# Line_Follower.net
KiCad netlist of a schematic drawn in EAGLE
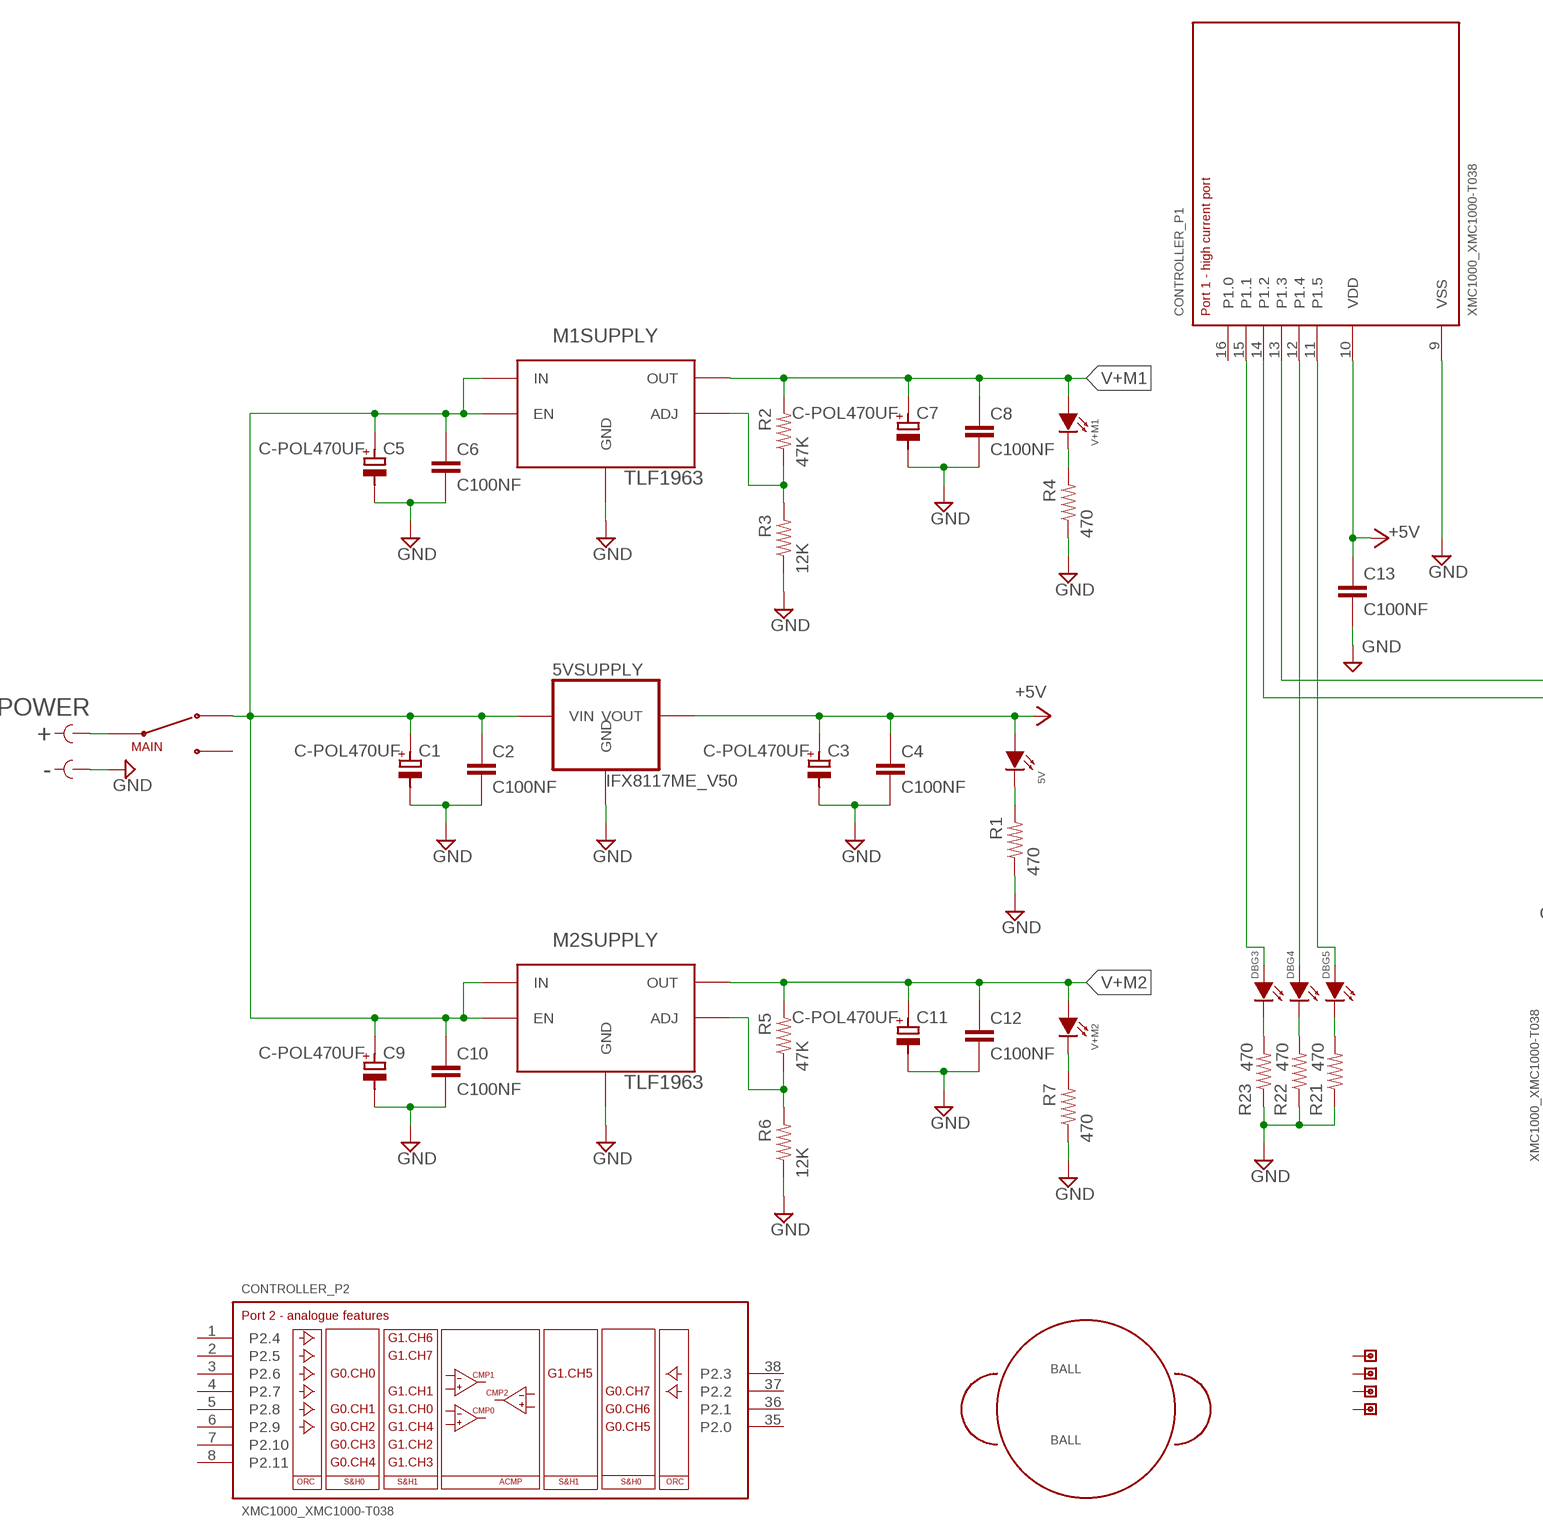
[diagram p0: schematic, sheet 1, part 1 of 2]
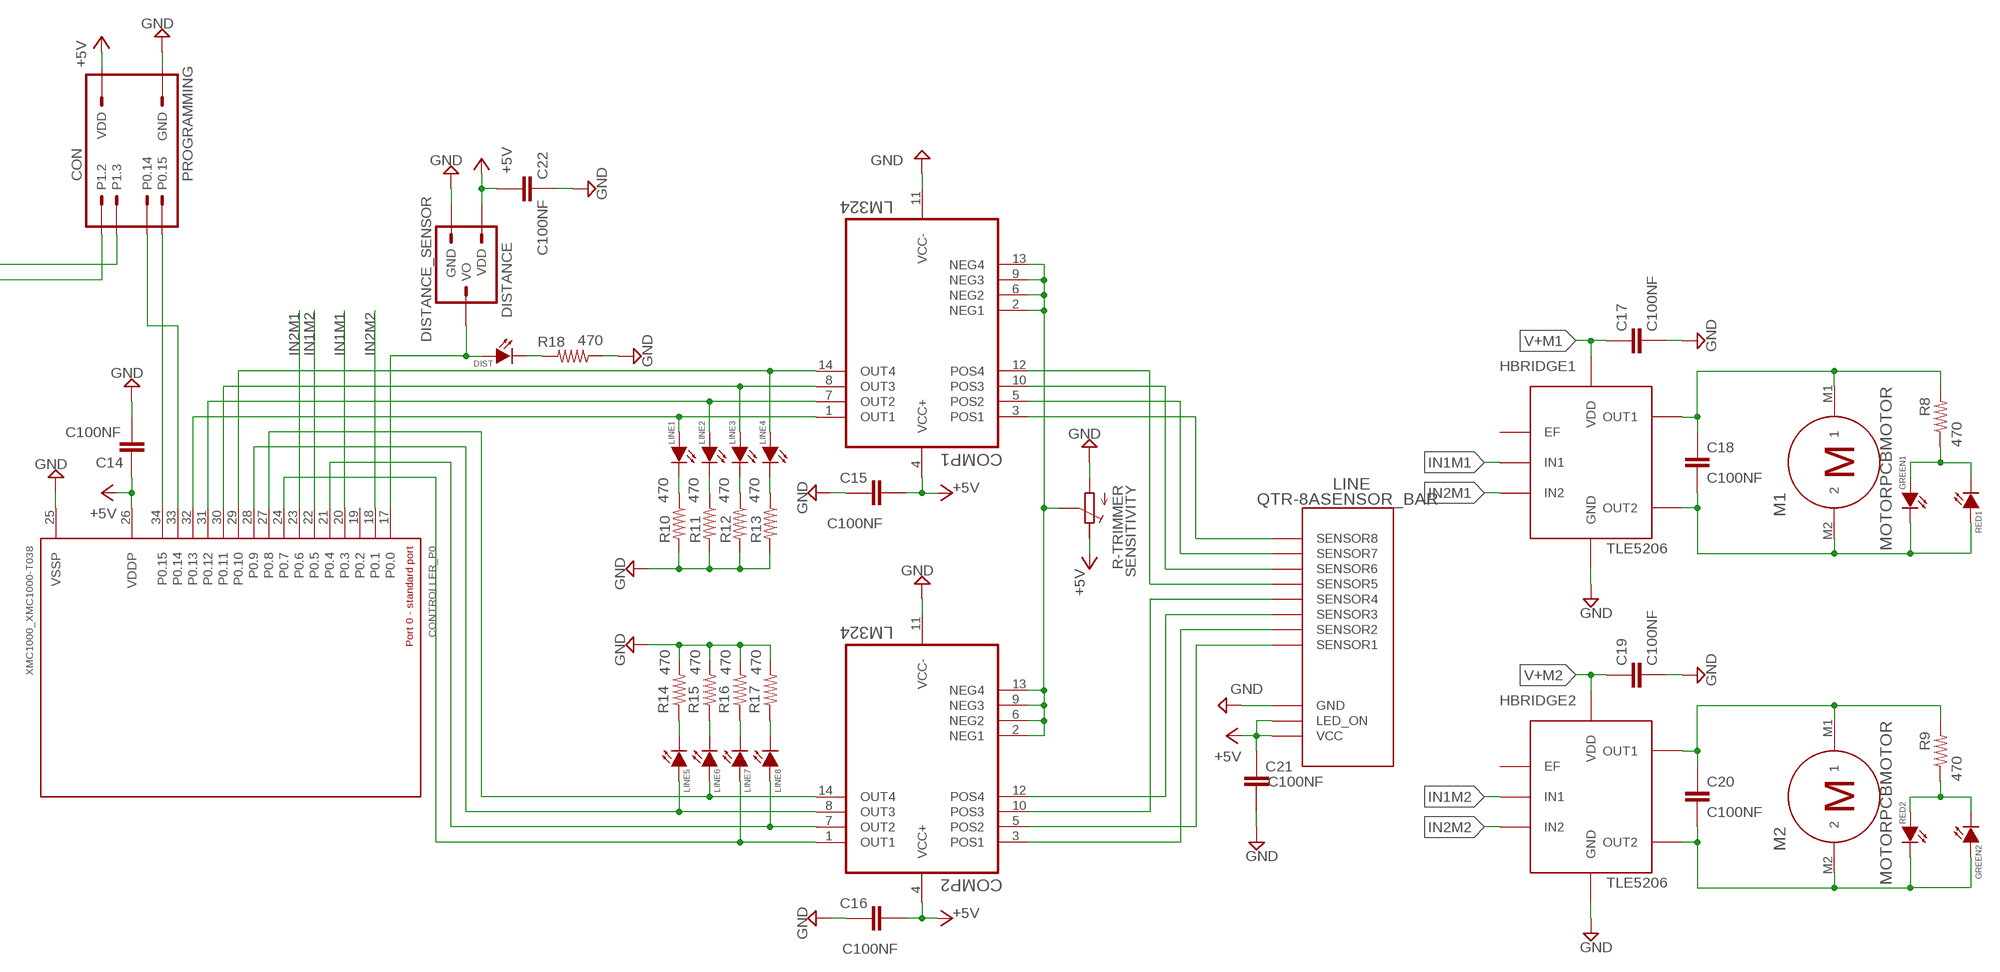
[diagram p1: schematic, sheet 1, part 2 of 2]

(export (version "E")
  (design (tool "Eeschema 10.0.6"))
  (components
    (comp (ref "5V")
      (value "LED")
      (footprint "eagle-import:CHIPLED_1206")
      (libsource (lib "eagle-import") (part "LED"))
    )
    (comp (ref "5VSUPPLY")
      (value "IFX8117ME_V50")
      (footprint "eagle-import:INF-PG-SOT223_SC-73_M_1PRIMARY")
      (libsource (lib "eagle-import") (part "IFX8117ME_V50"))
    )
    (comp (ref "BALL")
      (value "BALL")
      (footprint "eagle-import:BALL")
      (libsource (lib "eagle-import") (part "BALL"))
    )
    (comp (ref "C1")
      (value "C-POL470UF")
      (footprint "eagle-import:E3,5-8")
      (libsource (lib "eagle-import") (part "C-POL470UF"))
    )
    (comp (ref "C2")
      (value "C100NF")
      (footprint "eagle-import:C1206")
      (libsource (lib "eagle-import") (part "C100NF"))
    )
    (comp (ref "C3")
      (value "C-POL470UF")
      (footprint "eagle-import:E3,5-8")
      (libsource (lib "eagle-import") (part "C-POL470UF"))
    )
    (comp (ref "C4")
      (value "C100NF")
      (footprint "eagle-import:C1206")
      (libsource (lib "eagle-import") (part "C100NF"))
    )
    (comp (ref "C5")
      (value "C-POL470UF")
      (footprint "eagle-import:E3,5-8")
      (libsource (lib "eagle-import") (part "C-POL470UF"))
    )
    (comp (ref "C6")
      (value "C100NF")
      (footprint "eagle-import:C1206")
      (libsource (lib "eagle-import") (part "C100NF"))
    )
    (comp (ref "C7")
      (value "C-POL470UF")
      (footprint "eagle-import:E3,5-8")
      (libsource (lib "eagle-import") (part "C-POL470UF"))
    )
    (comp (ref "C8")
      (value "C100NF")
      (footprint "eagle-import:C1206")
      (libsource (lib "eagle-import") (part "C100NF"))
    )
    (comp (ref "C9")
      (value "C-POL470UF")
      (footprint "eagle-import:E3,5-8")
      (libsource (lib "eagle-import") (part "C-POL470UF"))
    )
    (comp (ref "C10")
      (value "C100NF")
      (footprint "eagle-import:C1206")
      (libsource (lib "eagle-import") (part "C100NF"))
    )
    (comp (ref "C11")
      (value "C-POL470UF")
      (footprint "eagle-import:E3,5-8")
      (libsource (lib "eagle-import") (part "C-POL470UF"))
    )
    (comp (ref "C12")
      (value "C100NF")
      (footprint "eagle-import:C1206")
      (libsource (lib "eagle-import") (part "C100NF"))
    )
    (comp (ref "C13")
      (value "C100NF")
      (footprint "eagle-import:C1206")
      (libsource (lib "eagle-import") (part "C100NF"))
    )
    (comp (ref "C14")
      (value "C100NF")
      (footprint "eagle-import:C1206")
      (libsource (lib "eagle-import") (part "C100NF"))
    )
    (comp (ref "C15")
      (value "C100NF")
      (footprint "eagle-import:C1206")
      (libsource (lib "eagle-import") (part "C100NF"))
    )
    (comp (ref "C16")
      (value "C100NF")
      (footprint "eagle-import:C1206")
      (libsource (lib "eagle-import") (part "C100NF"))
    )
    (comp (ref "C17")
      (value "C100NF")
      (footprint "eagle-import:C1206")
      (libsource (lib "eagle-import") (part "C100NF"))
    )
    (comp (ref "C18")
      (value "C100NF")
      (footprint "eagle-import:C1206")
      (libsource (lib "eagle-import") (part "C100NF"))
    )
    (comp (ref "C19")
      (value "C100NF")
      (footprint "eagle-import:C1206")
      (libsource (lib "eagle-import") (part "C100NF"))
    )
    (comp (ref "C20")
      (value "C100NF")
      (footprint "eagle-import:C1206")
      (libsource (lib "eagle-import") (part "C100NF"))
    )
    (comp (ref "C21")
      (value "C100NF")
      (footprint "eagle-import:C1206")
      (libsource (lib "eagle-import") (part "C100NF"))
    )
    (comp (ref "C22")
      (value "C100NF")
      (footprint "eagle-import:C1206")
      (libsource (lib "eagle-import") (part "C100NF"))
    )
    (comp (ref "COMP1")
      (value "LM324")
      (footprint "eagle-import:SO14")
      (libsource (lib "eagle-import") (part "LM324"))
    )
    (comp (ref "COMP2")
      (value "LM324")
      (footprint "eagle-import:SO14")
      (libsource (lib "eagle-import") (part "LM324"))
    )
    (comp (ref "CON")
      (value "PROGRAMMING")
      (footprint "eagle-import:MA05-2")
      (libsource (lib "eagle-import") (part "PROGRAMMING"))
    )
    (comp (ref "CONTROLLER")
      (value "XMC1000_XMC1000-T038")
      (footprint "eagle-import:XMC1000_P-TSSOP38-9")
      (libsource (lib "eagle-import") (part "XMC1000_XMC1000-T038"))
    )
    (comp (ref "DBG3")
      (value "LED")
      (footprint "eagle-import:CHIPLED_1206")
      (libsource (lib "eagle-import") (part "LED"))
    )
    (comp (ref "DBG4")
      (value "LED")
      (footprint "eagle-import:CHIPLED_1206")
      (libsource (lib "eagle-import") (part "LED"))
    )
    (comp (ref "DBG5")
      (value "LED")
      (footprint "eagle-import:CHIPLED_1206")
      (libsource (lib "eagle-import") (part "LED"))
    )
    (comp (ref "DIST")
      (value "LED")
      (footprint "eagle-import:CHIPLED_1206")
      (libsource (lib "eagle-import") (part "LED"))
    )
    (comp (ref "DISTANCE")
      (value "DISTANCE_SENSOR")
      (footprint "eagle-import:MA03-2")
      (libsource (lib "eagle-import") (part "DISTANCE_SENSOR"))
    )
    (comp (ref "GREEN1")
      (value "LED")
      (footprint "eagle-import:CHIPLED_1206")
      (libsource (lib "eagle-import") (part "LED"))
    )
    (comp (ref "GREEN2")
      (value "LED")
      (footprint "eagle-import:CHIPLED_1206")
      (libsource (lib "eagle-import") (part "LED"))
    )
    (comp (ref "HBRIDGE1")
      (value "TLE5206")
      (footprint "eagle-import:INF-PG-TO263-7-1_L_1PRIMARY")
      (libsource (lib "eagle-import") (part "TLE5206"))
    )
    (comp (ref "HBRIDGE2")
      (value "TLE5206")
      (footprint "eagle-import:INF-PG-TO263-7-1_L_1PRIMARY")
      (libsource (lib "eagle-import") (part "TLE5206"))
    )
    (comp (ref "LINE")
      (value "QTR-8ASENSOR_BAR")
      (footprint "eagle-import:QTR-8A")
      (libsource (lib "eagle-import") (part "QTR-8ASENSOR_BAR"))
    )
    (comp (ref "LINE1")
      (value "LED")
      (footprint "eagle-import:CHIPLED_1206")
      (libsource (lib "eagle-import") (part "LED"))
    )
    (comp (ref "LINE2")
      (value "LED")
      (footprint "eagle-import:CHIPLED_1206")
      (libsource (lib "eagle-import") (part "LED"))
    )
    (comp (ref "LINE3")
      (value "LED")
      (footprint "eagle-import:CHIPLED_1206")
      (libsource (lib "eagle-import") (part "LED"))
    )
    (comp (ref "LINE4")
      (value "LED")
      (footprint "eagle-import:CHIPLED_1206")
      (libsource (lib "eagle-import") (part "LED"))
    )
    (comp (ref "LINE5")
      (value "LED")
      (footprint "eagle-import:CHIPLED_1206")
      (libsource (lib "eagle-import") (part "LED"))
    )
    (comp (ref "LINE6")
      (value "LED")
      (footprint "eagle-import:CHIPLED_1206")
      (libsource (lib "eagle-import") (part "LED"))
    )
    (comp (ref "LINE7")
      (value "LED")
      (footprint "eagle-import:CHIPLED_1206")
      (libsource (lib "eagle-import") (part "LED"))
    )
    (comp (ref "LINE8")
      (value "LED")
      (footprint "eagle-import:CHIPLED_1206")
      (libsource (lib "eagle-import") (part "LED"))
    )
    (comp (ref "M1")
      (value "MOTORPCBMOTOR")
      (footprint "eagle-import:MICRO-MOTOR")
      (libsource (lib "eagle-import") (part "MOTORPCBMOTOR"))
    )
    (comp (ref "M1SUPPLY")
      (value "TLF1963")
      (footprint "eagle-import:INF-PG-TO252-5-11_L_1PRIMARY")
      (libsource (lib "eagle-import") (part "TLF1963"))
    )
    (comp (ref "M2")
      (value "MOTORPCBMOTOR")
      (footprint "eagle-import:MICRO-MOTOR")
      (libsource (lib "eagle-import") (part "MOTORPCBMOTOR"))
    )
    (comp (ref "M2SUPPLY")
      (value "TLF1963")
      (footprint "eagle-import:INF-PG-TO252-5-11_L_1PRIMARY")
      (libsource (lib "eagle-import") (part "TLF1963"))
    )
    (comp (ref "MAIN")
      (value "SWITCH1OFF2")
      (footprint "eagle-import:MS111")
      (libsource (lib "eagle-import") (part "SWITCH1OFF2"))
    )
    (comp (ref "POWER")
      (value "PWRCONCON1")
      (footprint "eagle-import:PWRCON")
      (libsource (lib "eagle-import") (part "PWRCONCON1"))
    )
    (comp (ref "R1")
      (value "470")
      (footprint "eagle-import:R1206")
      (libsource (lib "eagle-import") (part "R1206"))
    )
    (comp (ref "R2")
      (value "47K")
      (footprint "eagle-import:R1206")
      (libsource (lib "eagle-import") (part "R1206"))
    )
    (comp (ref "R3")
      (value "12K")
      (footprint "eagle-import:R1206")
      (libsource (lib "eagle-import") (part "R1206"))
    )
    (comp (ref "R4")
      (value "470")
      (footprint "eagle-import:R1206")
      (libsource (lib "eagle-import") (part "R1206"))
    )
    (comp (ref "R5")
      (value "47K")
      (footprint "eagle-import:R1206")
      (libsource (lib "eagle-import") (part "R1206"))
    )
    (comp (ref "R6")
      (value "12K")
      (footprint "eagle-import:R1206")
      (libsource (lib "eagle-import") (part "R1206"))
    )
    (comp (ref "R7")
      (value "470")
      (footprint "eagle-import:R1206")
      (libsource (lib "eagle-import") (part "R1206"))
    )
    (comp (ref "R8")
      (value "470")
      (footprint "eagle-import:R1206")
      (libsource (lib "eagle-import") (part "R1206"))
    )
    (comp (ref "R9")
      (value "470")
      (footprint "eagle-import:R1206")
      (libsource (lib "eagle-import") (part "R1206"))
    )
    (comp (ref "R10")
      (value "470")
      (footprint "eagle-import:R1206")
      (libsource (lib "eagle-import") (part "R1206"))
    )
    (comp (ref "R11")
      (value "470")
      (footprint "eagle-import:R1206")
      (libsource (lib "eagle-import") (part "R1206"))
    )
    (comp (ref "R12")
      (value "470")
      (footprint "eagle-import:R1206")
      (libsource (lib "eagle-import") (part "R1206"))
    )
    (comp (ref "R13")
      (value "470")
      (footprint "eagle-import:R1206")
      (libsource (lib "eagle-import") (part "R1206"))
    )
    (comp (ref "R14")
      (value "470")
      (footprint "eagle-import:R1206")
      (libsource (lib "eagle-import") (part "R1206"))
    )
    (comp (ref "R15")
      (value "470")
      (footprint "eagle-import:R1206")
      (libsource (lib "eagle-import") (part "R1206"))
    )
    (comp (ref "R16")
      (value "470")
      (footprint "eagle-import:R1206")
      (libsource (lib "eagle-import") (part "R1206"))
    )
    (comp (ref "R17")
      (value "470")
      (footprint "eagle-import:R1206")
      (libsource (lib "eagle-import") (part "R1206"))
    )
    (comp (ref "R18")
      (value "470")
      (footprint "eagle-import:R1206")
      (libsource (lib "eagle-import") (part "R1206"))
    )
    (comp (ref "R21")
      (value "470")
      (footprint "eagle-import:R1206")
      (libsource (lib "eagle-import") (part "R1206"))
    )
    (comp (ref "R22")
      (value "470")
      (footprint "eagle-import:R1206")
      (libsource (lib "eagle-import") (part "R1206"))
    )
    (comp (ref "R23")
      (value "470")
      (footprint "eagle-import:R1206")
      (libsource (lib "eagle-import") (part "R1206"))
    )
    (comp (ref "RED1")
      (value "LED")
      (footprint "eagle-import:CHIPLED_1206")
      (libsource (lib "eagle-import") (part "LED"))
    )
    (comp (ref "RED2")
      (value "LED")
      (footprint "eagle-import:CHIPLED_1206")
      (libsource (lib "eagle-import") (part "LED"))
    )
    (comp (ref "SENSITIVITY")
      (value "R-TRIMMER")
      (footprint "eagle-import:TRIMMER")
      (libsource (lib "eagle-import") (part "R-TRIMMER"))
    )
    (comp (ref "U$2")
      (value "SPACER")
      (footprint "eagle-import:SPACERS_M3")
      (libsource (lib "eagle-import") (part "SPACER"))
    )
    (comp (ref "U$3")
      (value "SPACER")
      (footprint "eagle-import:SPACERS_M3")
      (libsource (lib "eagle-import") (part "SPACER"))
    )
    (comp (ref "U$4")
      (value "SPACER")
      (footprint "eagle-import:SPACERS_M3")
      (libsource (lib "eagle-import") (part "SPACER"))
    )
    (comp (ref "U$5")
      (value "SPACER")
      (footprint "eagle-import:SPACERS_M3")
      (libsource (lib "eagle-import") (part "SPACER"))
    )
    (comp (ref "V+M1")
      (value "LED")
      (footprint "eagle-import:CHIPLED_1206")
      (libsource (lib "eagle-import") (part "LED"))
    )
    (comp (ref "V+M2")
      (value "LED")
      (footprint "eagle-import:CHIPLED_1206")
      (libsource (lib "eagle-import") (part "LED"))
    )
  )
  (nets
    (net (code "1") (name "+5V") (class "Default")
      (node (ref "5V") (pin "A") (pinfunction "A_A") (pintype "bidirectional"))
      (node (ref "5VSUPPLY") (pin "2") (pinfunction "VOUT_2") (pintype "power_in"))
      (node (ref "5VSUPPLY") (pin "4") (pinfunction "VOUT_4") (pintype "power_in"))
      (node (ref "C13") (pin "1") (pinfunction "1_1") (pintype "passive"))
      (node (ref "C14") (pin "2") (pinfunction "2_2") (pintype "passive"))
      (node (ref "C15") (pin "2") (pinfunction "2_2") (pintype "passive"))
      (node (ref "C16") (pin "2") (pinfunction "2_2") (pintype "passive"))
      (node (ref "C21") (pin "1") (pinfunction "1_1") (pintype "passive"))
      (node (ref "C22") (pin "1") (pinfunction "1_1") (pintype "passive"))
      (node (ref "C3") (pin "+") (pinfunction "+_+") (pintype "passive"))
      (node (ref "C4") (pin "1") (pinfunction "1_1") (pintype "passive"))
      (node (ref "COMP1") (pin "4") (pinfunction "VCC+_4") (pintype "power_in"))
      (node (ref "COMP2") (pin "4") (pinfunction "VCC+_4") (pintype "power_in"))
      (node (ref "CON") (pin "5") (pinfunction "VDD_5") (pintype "passive"))
      (node (ref "CON") (pin "6") (pinfunction "VDD_6") (pintype "passive"))
      (node (ref "CONTROLLER") (pin "10") (pinfunction "VDD_10") (pintype "power_in"))
      (node (ref "CONTROLLER") (pin "26") (pinfunction "VDDP_26") (pintype "power_in"))
      (node (ref "DISTANCE") (pin "1") (pinfunction "VDD_1") (pintype "passive"))
      (node (ref "LINE") (pin "P$2") (pinfunction "LED_ON_P$2") (pintype "input"))
      (node (ref "LINE") (pin "P$4") (pinfunction "VCC_P$4") (pintype "power_in"))
      (node (ref "SENSITIVITY") (pin "2") (pinfunction "E_2") (pintype "passive"))
    )
    (net (code "2") (name "GND") (class "Default")
      (node (ref "5VSUPPLY") (pin "1") (pinfunction "GND_1") (pintype "power_in"))
      (node (ref "C1") (pin "-") (pinfunction "-_-") (pintype "passive"))
      (node (ref "C10") (pin "2") (pinfunction "2_2") (pintype "passive"))
      (node (ref "C11") (pin "-") (pinfunction "-_-") (pintype "passive"))
      (node (ref "C12") (pin "2") (pinfunction "2_2") (pintype "passive"))
      (node (ref "C13") (pin "2") (pinfunction "2_2") (pintype "passive"))
      (node (ref "C14") (pin "1") (pinfunction "1_1") (pintype "passive"))
      (node (ref "C15") (pin "1") (pinfunction "1_1") (pintype "passive"))
      (node (ref "C16") (pin "1") (pinfunction "1_1") (pintype "passive"))
      (node (ref "C17") (pin "2") (pinfunction "2_2") (pintype "passive"))
      (node (ref "C19") (pin "2") (pinfunction "2_2") (pintype "passive"))
      (node (ref "C2") (pin "2") (pinfunction "2_2") (pintype "passive"))
      (node (ref "C21") (pin "2") (pinfunction "2_2") (pintype "passive"))
      (node (ref "C22") (pin "2") (pinfunction "2_2") (pintype "passive"))
      (node (ref "C3") (pin "-") (pinfunction "-_-") (pintype "passive"))
      (node (ref "C4") (pin "2") (pinfunction "2_2") (pintype "passive"))
      (node (ref "C5") (pin "-") (pinfunction "-_-") (pintype "passive"))
      (node (ref "C6") (pin "2") (pinfunction "2_2") (pintype "passive"))
      (node (ref "C7") (pin "-") (pinfunction "-_-") (pintype "passive"))
      (node (ref "C8") (pin "2") (pinfunction "2_2") (pintype "passive"))
      (node (ref "C9") (pin "-") (pinfunction "-_-") (pintype "passive"))
      (node (ref "COMP1") (pin "11") (pinfunction "VCC-_11") (pintype "power_in"))
      (node (ref "COMP2") (pin "11") (pinfunction "VCC-_11") (pintype "power_in"))
      (node (ref "CON") (pin "10") (pinfunction "GND_10") (pintype "passive"))
      (node (ref "CON") (pin "3") (pinfunction "GND_3") (pintype "passive"))
      (node (ref "CON") (pin "4") (pinfunction "GND_4") (pintype "passive"))
      (node (ref "CON") (pin "9") (pinfunction "GND_9") (pintype "passive"))
      (node (ref "CONTROLLER") (pin "25") (pinfunction "VSSP_25") (pintype "power_in"))
      (node (ref "CONTROLLER") (pin "9") (pinfunction "VSS_9") (pintype "power_in"))
      (node (ref "DISTANCE") (pin "3") (pinfunction "GND_3") (pintype "passive"))
      (node (ref "DISTANCE") (pin "4") (pinfunction "GND_4") (pintype "passive"))
      (node (ref "DISTANCE") (pin "5") (pinfunction "GND_5") (pintype "passive"))
      (node (ref "DISTANCE") (pin "6") (pinfunction "GND_6") (pintype "passive"))
      (node (ref "HBRIDGE1") (pin "4") (pinfunction "GND_4") (pintype "power_in"))
      (node (ref "HBRIDGE1") (pin "8") (pinfunction "GND_8") (pintype "power_in"))
      (node (ref "HBRIDGE2") (pin "4") (pinfunction "GND_4") (pintype "power_in"))
      (node (ref "HBRIDGE2") (pin "8") (pinfunction "GND_8") (pintype "power_in"))
      (node (ref "LINE") (pin "P$10") (pinfunction "GND_P$10") (pintype "power_in"))
      (node (ref "LINE") (pin "P$12") (pinfunction "GND_P$12") (pintype "power_in"))
      (node (ref "LINE") (pin "P$14") (pinfunction "GND_P$14") (pintype "power_in"))
      (node (ref "LINE") (pin "P$16") (pinfunction "GND_P$16") (pintype "power_in"))
      (node (ref "LINE") (pin "P$6") (pinfunction "GND_P$6") (pintype "power_in"))
      (node (ref "LINE") (pin "P$8") (pinfunction "GND_P$8") (pintype "power_in"))
      (node (ref "M1SUPPLY") (pin "3") (pinfunction "GND_3") (pintype "power_in"))
      (node (ref "M2SUPPLY") (pin "3") (pinfunction "GND_3") (pintype "power_in"))
      (node (ref "POWER") (pin "-") (pinfunction "-_-") (pintype "bidirectional"))
      (node (ref "R1") (pin "1") (pinfunction "P$1_1") (pintype "passive"))
      (node (ref "R10") (pin "2") (pinfunction "P$2_2") (pintype "passive"))
      (node (ref "R11") (pin "2") (pinfunction "P$2_2") (pintype "passive"))
      (node (ref "R12") (pin "2") (pinfunction "P$2_2") (pintype "passive"))
      (node (ref "R13") (pin "2") (pinfunction "P$2_2") (pintype "passive"))
      (node (ref "R14") (pin "2") (pinfunction "P$2_2") (pintype "passive"))
      (node (ref "R15") (pin "2") (pinfunction "P$2_2") (pintype "passive"))
      (node (ref "R16") (pin "2") (pinfunction "P$2_2") (pintype "passive"))
      (node (ref "R17") (pin "2") (pinfunction "P$2_2") (pintype "passive"))
      (node (ref "R18") (pin "1") (pinfunction "P$1_1") (pintype "passive"))
      (node (ref "R21") (pin "1") (pinfunction "P$1_1") (pintype "passive"))
      (node (ref "R22") (pin "1") (pinfunction "P$1_1") (pintype "passive"))
      (node (ref "R23") (pin "1") (pinfunction "P$1_1") (pintype "passive"))
      (node (ref "R3") (pin "1") (pinfunction "P$1_1") (pintype "passive"))
      (node (ref "R4") (pin "1") (pinfunction "P$1_1") (pintype "passive"))
      (node (ref "R6") (pin "1") (pinfunction "P$1_1") (pintype "passive"))
      (node (ref "R7") (pin "1") (pinfunction "P$1_1") (pintype "passive"))
      (node (ref "SENSITIVITY") (pin "1") (pinfunction "A_1") (pintype "passive"))
    )
    (net (code "3") (name "IN1M1") (class "Default")
      (node (ref "CONTROLLER") (pin "20") (pinfunction "P0.3_20") (pintype "bidirectional"))
      (node (ref "HBRIDGE1") (pin "3") (pinfunction "IN1_3") (pintype "input"))
    )
    (net (code "4") (name "IN1M2") (class "Default")
      (node (ref "CONTROLLER") (pin "22") (pinfunction "P0.5_22") (pintype "bidirectional"))
      (node (ref "HBRIDGE2") (pin "3") (pinfunction "IN1_3") (pintype "input"))
    )
    (net (code "5") (name "IN2M1") (class "Default")
      (node (ref "CONTROLLER") (pin "23") (pinfunction "P0.6_23") (pintype "bidirectional"))
      (node (ref "HBRIDGE1") (pin "5") (pinfunction "IN2_5") (pintype "input"))
    )
    (net (code "6") (name "IN2M2") (class "Default")
      (node (ref "CONTROLLER") (pin "18") (pinfunction "P0.1_18") (pintype "bidirectional"))
      (node (ref "HBRIDGE2") (pin "5") (pinfunction "IN2_5") (pintype "input"))
    )
    (net (code "7") (name "Net-(5V-K)") (class "Default")
      (node (ref "5V") (pin "C") (pinfunction "K_C") (pintype "bidirectional"))
      (node (ref "R1") (pin "2") (pinfunction "P$2_2") (pintype "passive"))
    )
    (net (code "8") (name "Net-(5VSUPPLY-VIN)") (class "Default")
      (node (ref "5VSUPPLY") (pin "3") (pinfunction "VIN_3") (pintype "power_in"))
      (node (ref "C1") (pin "+") (pinfunction "+_+") (pintype "passive"))
      (node (ref "C10") (pin "1") (pinfunction "1_1") (pintype "passive"))
      (node (ref "C2") (pin "1") (pinfunction "1_1") (pintype "passive"))
      (node (ref "C5") (pin "+") (pinfunction "+_+") (pintype "passive"))
      (node (ref "C6") (pin "1") (pinfunction "1_1") (pintype "passive"))
      (node (ref "C9") (pin "+") (pinfunction "+_+") (pintype "passive"))
      (node (ref "M1SUPPLY") (pin "1") (pinfunction "EN_1") (pintype "bidirectional"))
      (node (ref "M1SUPPLY") (pin "2") (pinfunction "IN_2") (pintype "power_in"))
      (node (ref "M2SUPPLY") (pin "1") (pinfunction "EN_1") (pintype "bidirectional"))
      (node (ref "M2SUPPLY") (pin "2") (pinfunction "IN_2") (pintype "power_in"))
      (node (ref "MAIN") (pin "P$1") (pinfunction "1_P$1") (pintype "bidirectional"))
    )
    (net (code "9") (name "Net-(COMP1-NEG1)") (class "Default")
      (node (ref "COMP1") (pin "13") (pinfunction "NEG4_13") (pintype "input"))
      (node (ref "COMP1") (pin "2") (pinfunction "NEG1_2") (pintype "input"))
      (node (ref "COMP1") (pin "6") (pinfunction "NEG2_6") (pintype "input"))
      (node (ref "COMP1") (pin "9") (pinfunction "NEG3_9") (pintype "input"))
      (node (ref "COMP2") (pin "13") (pinfunction "NEG4_13") (pintype "input"))
      (node (ref "COMP2") (pin "2") (pinfunction "NEG1_2") (pintype "input"))
      (node (ref "COMP2") (pin "6") (pinfunction "NEG2_6") (pintype "input"))
      (node (ref "COMP2") (pin "9") (pinfunction "NEG3_9") (pintype "input"))
      (node (ref "SENSITIVITY") (pin "3") (pinfunction "S_3") (pintype "passive"))
    )
    (net (code "10") (name "Net-(COMP1-OUT1)") (class "Default")
      (node (ref "COMP1") (pin "1") (pinfunction "OUT1_1") (pintype "output"))
      (node (ref "CONTROLLER") (pin "32") (pinfunction "P0.13_32") (pintype "bidirectional"))
      (node (ref "LINE1") (pin "A") (pinfunction "A_A") (pintype "bidirectional"))
    )
    (net (code "11") (name "Net-(COMP1-OUT2)") (class "Default")
      (node (ref "COMP1") (pin "7") (pinfunction "OUT2_7") (pintype "output"))
      (node (ref "CONTROLLER") (pin "31") (pinfunction "P0.12_31") (pintype "bidirectional"))
      (node (ref "LINE2") (pin "A") (pinfunction "A_A") (pintype "bidirectional"))
    )
    (net (code "12") (name "Net-(COMP1-OUT3)") (class "Default")
      (node (ref "COMP1") (pin "8") (pinfunction "OUT3_8") (pintype "output"))
      (node (ref "CONTROLLER") (pin "30") (pinfunction "P0.11_30") (pintype "bidirectional"))
      (node (ref "LINE3") (pin "A") (pinfunction "A_A") (pintype "bidirectional"))
    )
    (net (code "13") (name "Net-(COMP1-OUT4)") (class "Default")
      (node (ref "COMP1") (pin "14") (pinfunction "OUT4_14") (pintype "output"))
      (node (ref "CONTROLLER") (pin "29") (pinfunction "P0.10_29") (pintype "bidirectional"))
      (node (ref "LINE4") (pin "A") (pinfunction "A_A") (pintype "bidirectional"))
    )
    (net (code "14") (name "Net-(COMP1-POS1)") (class "Default")
      (node (ref "COMP1") (pin "3") (pinfunction "POS1_3") (pintype "input"))
      (node (ref "LINE") (pin "P$15") (pinfunction "SENSOR8_P$15") (pintype "output"))
    )
    (net (code "15") (name "Net-(COMP1-POS2)") (class "Default")
      (node (ref "COMP1") (pin "5") (pinfunction "POS2_5") (pintype "input"))
      (node (ref "LINE") (pin "P$13") (pinfunction "SENSOR7_P$13") (pintype "output"))
    )
    (net (code "16") (name "Net-(COMP1-POS3)") (class "Default")
      (node (ref "COMP1") (pin "10") (pinfunction "POS3_10") (pintype "input"))
      (node (ref "LINE") (pin "P$11") (pinfunction "SENSOR6_P$11") (pintype "output"))
    )
    (net (code "17") (name "Net-(COMP1-POS4)") (class "Default")
      (node (ref "COMP1") (pin "12") (pinfunction "POS4_12") (pintype "input"))
      (node (ref "LINE") (pin "P$9") (pinfunction "SENSOR5_P$9") (pintype "output"))
    )
    (net (code "18") (name "Net-(COMP2-OUT1)") (class "Default")
      (node (ref "COMP2") (pin "1") (pinfunction "OUT1_1") (pintype "output"))
      (node (ref "CONTROLLER") (pin "24") (pinfunction "P0.7_24") (pintype "bidirectional"))
      (node (ref "LINE7") (pin "A") (pinfunction "A_A") (pintype "bidirectional"))
    )
    (net (code "19") (name "Net-(COMP2-OUT2)") (class "Default")
      (node (ref "COMP2") (pin "7") (pinfunction "OUT2_7") (pintype "output"))
      (node (ref "CONTROLLER") (pin "21") (pinfunction "P0.4_21") (pintype "bidirectional"))
      (node (ref "LINE8") (pin "A") (pinfunction "A_A") (pintype "bidirectional"))
    )
    (net (code "20") (name "Net-(COMP2-OUT3)") (class "Default")
      (node (ref "COMP2") (pin "8") (pinfunction "OUT3_8") (pintype "output"))
      (node (ref "CONTROLLER") (pin "28") (pinfunction "P0.9_28") (pintype "bidirectional"))
      (node (ref "LINE5") (pin "A") (pinfunction "A_A") (pintype "bidirectional"))
    )
    (net (code "21") (name "Net-(COMP2-OUT4)") (class "Default")
      (node (ref "COMP2") (pin "14") (pinfunction "OUT4_14") (pintype "output"))
      (node (ref "CONTROLLER") (pin "27") (pinfunction "P0.8_27") (pintype "bidirectional"))
      (node (ref "LINE6") (pin "A") (pinfunction "A_A") (pintype "bidirectional"))
    )
    (net (code "22") (name "Net-(COMP2-POS1)") (class "Default")
      (node (ref "COMP2") (pin "3") (pinfunction "POS1_3") (pintype "input"))
      (node (ref "LINE") (pin "P$3") (pinfunction "SENSOR2_P$3") (pintype "output"))
    )
    (net (code "23") (name "Net-(COMP2-POS2)") (class "Default")
      (node (ref "COMP2") (pin "5") (pinfunction "POS2_5") (pintype "input"))
      (node (ref "LINE") (pin "P$1") (pinfunction "SENSOR1_P$1") (pintype "output"))
    )
    (net (code "24") (name "Net-(COMP2-POS3)") (class "Default")
      (node (ref "COMP2") (pin "10") (pinfunction "POS3_10") (pintype "input"))
      (node (ref "LINE") (pin "P$7") (pinfunction "SENSOR4_P$7") (pintype "output"))
    )
    (net (code "25") (name "Net-(COMP2-POS4)") (class "Default")
      (node (ref "COMP2") (pin "12") (pinfunction "POS4_12") (pintype "input"))
      (node (ref "LINE") (pin "P$5") (pinfunction "SENSOR3_P$5") (pintype "output"))
    )
    (net (code "26") (name "Net-(CON-P0.14)") (class "Default")
      (node (ref "CON") (pin "2") (pinfunction "P0.14_2") (pintype "passive"))
      (node (ref "CONTROLLER") (pin "33") (pinfunction "P0.14_33") (pintype "bidirectional"))
    )
    (net (code "27") (name "Net-(CON-P0.15)") (class "Default")
      (node (ref "CON") (pin "1") (pinfunction "P0.15_1") (pintype "passive"))
      (node (ref "CONTROLLER") (pin "34") (pinfunction "P0.15_34") (pintype "bidirectional"))
    )
    (net (code "28") (name "Net-(CON-P1.2)") (class "Default")
      (node (ref "CON") (pin "8") (pinfunction "P1.2_8") (pintype "passive"))
      (node (ref "CONTROLLER") (pin "14") (pinfunction "P1.2_14") (pintype "bidirectional"))
    )
    (net (code "29") (name "Net-(CON-P1.3)") (class "Default")
      (node (ref "CON") (pin "7") (pinfunction "P1.3_7") (pintype "passive"))
      (node (ref "CONTROLLER") (pin "13") (pinfunction "P1.3_13") (pintype "bidirectional"))
    )
    (net (code "30") (name "Net-(CONTROLLERA-P0.0)") (class "Default")
      (node (ref "CONTROLLER") (pin "17") (pinfunction "P0.0_17") (pintype "bidirectional"))
      (node (ref "DIST") (pin "A") (pinfunction "A_A") (pintype "bidirectional"))
      (node (ref "DISTANCE") (pin "2") (pinfunction "VO_2") (pintype "passive"))
    )
    (net (code "31") (name "Net-(CONTROLLERB-P1.1)") (class "Default")
      (node (ref "CONTROLLER") (pin "15") (pinfunction "P1.1_15") (pintype "bidirectional"))
      (node (ref "DBG3") (pin "A") (pinfunction "A_A") (pintype "bidirectional"))
    )
    (net (code "32") (name "Net-(CONTROLLERB-P1.4)") (class "Default")
      (node (ref "CONTROLLER") (pin "12") (pinfunction "P1.4_12") (pintype "bidirectional"))
      (node (ref "DBG4") (pin "A") (pinfunction "A_A") (pintype "bidirectional"))
    )
    (net (code "33") (name "Net-(CONTROLLERB-P1.5)") (class "Default")
      (node (ref "CONTROLLER") (pin "11") (pinfunction "P1.5_11") (pintype "bidirectional"))
      (node (ref "DBG5") (pin "A") (pinfunction "A_A") (pintype "bidirectional"))
    )
    (net (code "34") (name "Net-(DBG3-K)") (class "Default")
      (node (ref "DBG3") (pin "C") (pinfunction "K_C") (pintype "bidirectional"))
      (node (ref "R23") (pin "2") (pinfunction "P$2_2") (pintype "passive"))
    )
    (net (code "35") (name "Net-(DBG4-K)") (class "Default")
      (node (ref "DBG4") (pin "C") (pinfunction "K_C") (pintype "bidirectional"))
      (node (ref "R22") (pin "2") (pinfunction "P$2_2") (pintype "passive"))
    )
    (net (code "36") (name "Net-(DBG5-K)") (class "Default")
      (node (ref "DBG5") (pin "C") (pinfunction "K_C") (pintype "bidirectional"))
      (node (ref "R21") (pin "2") (pinfunction "P$2_2") (pintype "passive"))
    )
    (net (code "37") (name "Net-(DIST-K)") (class "Default")
      (node (ref "DIST") (pin "C") (pinfunction "K_C") (pintype "bidirectional"))
      (node (ref "R18") (pin "2") (pinfunction "P$2_2") (pintype "passive"))
    )
    (net (code "38") (name "Net-(GREEN1-K)") (class "Default")
      (node (ref "C18") (pin "2") (pinfunction "2_2") (pintype "passive"))
      (node (ref "GREEN1") (pin "C") (pinfunction "K_C") (pintype "bidirectional"))
      (node (ref "HBRIDGE1") (pin "7") (pinfunction "OUT2_7") (pintype "output"))
      (node (ref "M1") (pin "M2") (pinfunction "2_M2") (pintype "bidirectional"))
      (node (ref "RED1") (pin "A") (pinfunction "A_A") (pintype "bidirectional"))
    )
    (net (code "39") (name "Net-(GREEN2-K)") (class "Default")
      (node (ref "GREEN2") (pin "C") (pinfunction "K_C") (pintype "bidirectional"))
      (node (ref "R9") (pin "1") (pinfunction "P$1_1") (pintype "passive"))
      (node (ref "RED2") (pin "A") (pinfunction "A_A") (pintype "bidirectional"))
    )
    (net (code "40") (name "Net-(HBRIDGE1-OUT1)") (class "Default")
      (node (ref "C18") (pin "1") (pinfunction "1_1") (pintype "passive"))
      (node (ref "HBRIDGE1") (pin "1") (pinfunction "OUT1_1") (pintype "output"))
      (node (ref "M1") (pin "M1") (pinfunction "1_M1") (pintype "bidirectional"))
      (node (ref "R8") (pin "2") (pinfunction "P$2_2") (pintype "passive"))
    )
    (net (code "41") (name "Net-(HBRIDGE2-OUT1)") (class "Default")
      (node (ref "C20") (pin "1") (pinfunction "1_1") (pintype "passive"))
      (node (ref "HBRIDGE2") (pin "1") (pinfunction "OUT1_1") (pintype "output"))
      (node (ref "M2") (pin "M1") (pinfunction "1_M1") (pintype "bidirectional"))
      (node (ref "R9") (pin "2") (pinfunction "P$2_2") (pintype "passive"))
    )
    (net (code "42") (name "Net-(HBRIDGE2-OUT2)") (class "Default")
      (node (ref "C20") (pin "2") (pinfunction "2_2") (pintype "passive"))
      (node (ref "GREEN2") (pin "A") (pinfunction "A_A") (pintype "bidirectional"))
      (node (ref "HBRIDGE2") (pin "7") (pinfunction "OUT2_7") (pintype "output"))
      (node (ref "M2") (pin "M2") (pinfunction "2_M2") (pintype "bidirectional"))
      (node (ref "RED2") (pin "C") (pinfunction "K_C") (pintype "bidirectional"))
    )
    (net (code "43") (name "Net-(LINE1-K)") (class "Default")
      (node (ref "LINE1") (pin "C") (pinfunction "K_C") (pintype "bidirectional"))
      (node (ref "R10") (pin "1") (pinfunction "P$1_1") (pintype "passive"))
    )
    (net (code "44") (name "Net-(LINE2-K)") (class "Default")
      (node (ref "LINE2") (pin "C") (pinfunction "K_C") (pintype "bidirectional"))
      (node (ref "R11") (pin "1") (pinfunction "P$1_1") (pintype "passive"))
    )
    (net (code "45") (name "Net-(LINE3-K)") (class "Default")
      (node (ref "LINE3") (pin "C") (pinfunction "K_C") (pintype "bidirectional"))
      (node (ref "R12") (pin "1") (pinfunction "P$1_1") (pintype "passive"))
    )
    (net (code "46") (name "Net-(LINE4-K)") (class "Default")
      (node (ref "LINE4") (pin "C") (pinfunction "K_C") (pintype "bidirectional"))
      (node (ref "R13") (pin "1") (pinfunction "P$1_1") (pintype "passive"))
    )
    (net (code "47") (name "Net-(LINE5-K)") (class "Default")
      (node (ref "LINE5") (pin "C") (pinfunction "K_C") (pintype "bidirectional"))
      (node (ref "R14") (pin "1") (pinfunction "P$1_1") (pintype "passive"))
    )
    (net (code "48") (name "Net-(LINE6-K)") (class "Default")
      (node (ref "LINE6") (pin "C") (pinfunction "K_C") (pintype "bidirectional"))
      (node (ref "R15") (pin "1") (pinfunction "P$1_1") (pintype "passive"))
    )
    (net (code "49") (name "Net-(LINE7-K)") (class "Default")
      (node (ref "LINE7") (pin "C") (pinfunction "K_C") (pintype "bidirectional"))
      (node (ref "R16") (pin "1") (pinfunction "P$1_1") (pintype "passive"))
    )
    (net (code "50") (name "Net-(LINE8-K)") (class "Default")
      (node (ref "LINE8") (pin "C") (pinfunction "K_C") (pintype "bidirectional"))
      (node (ref "R17") (pin "1") (pinfunction "P$1_1") (pintype "passive"))
    )
    (net (code "51") (name "Net-(M1SUPPLY-ADJ)") (class "Default")
      (node (ref "M1SUPPLY") (pin "5") (pinfunction "ADJ_5") (pintype "bidirectional"))
      (node (ref "R2") (pin "1") (pinfunction "P$1_1") (pintype "passive"))
      (node (ref "R3") (pin "2") (pinfunction "P$2_2") (pintype "passive"))
    )
    (net (code "52") (name "Net-(M2SUPPLY-ADJ)") (class "Default")
      (node (ref "M2SUPPLY") (pin "5") (pinfunction "ADJ_5") (pintype "bidirectional"))
      (node (ref "R5") (pin "1") (pinfunction "P$1_1") (pintype "passive"))
      (node (ref "R6") (pin "2") (pinfunction "P$2_2") (pintype "passive"))
    )
    (net (code "53") (name "Net-(MAIN-COM)") (class "Default")
      (node (ref "MAIN") (pin "P$2") (pinfunction "COM_P$2") (pintype "bidirectional"))
      (node (ref "POWER") (pin "+") (pinfunction "+_+") (pintype "bidirectional"))
    )
    (net (code "54") (name "Net-(R4-P$2)") (class "Default")
      (node (ref "R4") (pin "2") (pinfunction "P$2_2") (pintype "passive"))
      (node (ref "V+M1") (pin "C") (pinfunction "K_C") (pintype "bidirectional"))
    )
    (net (code "55") (name "Net-(R7-P$2)") (class "Default")
      (node (ref "R7") (pin "2") (pinfunction "P$2_2") (pintype "passive"))
      (node (ref "V+M2") (pin "C") (pinfunction "K_C") (pintype "bidirectional"))
    )
    (net (code "56") (name "Net-(R8-P$1)") (class "Default")
      (node (ref "GREEN1") (pin "A") (pinfunction "A_A") (pintype "bidirectional"))
      (node (ref "R8") (pin "1") (pinfunction "P$1_1") (pintype "passive"))
      (node (ref "RED1") (pin "C") (pinfunction "K_C") (pintype "bidirectional"))
    )
    (net (code "57") (name "V+M1") (class "Default")
      (node (ref "C17") (pin "1") (pinfunction "1_1") (pintype "passive"))
      (node (ref "C7") (pin "+") (pinfunction "+_+") (pintype "passive"))
      (node (ref "C8") (pin "1") (pinfunction "1_1") (pintype "passive"))
      (node (ref "HBRIDGE1") (pin "6") (pinfunction "VDD_6") (pintype "power_in"))
      (node (ref "M1SUPPLY") (pin "4") (pinfunction "OUT_4") (pintype "power_in"))
      (node (ref "R2") (pin "2") (pinfunction "P$2_2") (pintype "passive"))
      (node (ref "V+M1") (pin "A") (pinfunction "A_A") (pintype "bidirectional"))
    )
    (net (code "58") (name "V+M2") (class "Default")
      (node (ref "C11") (pin "+") (pinfunction "+_+") (pintype "passive"))
      (node (ref "C12") (pin "1") (pinfunction "1_1") (pintype "passive"))
      (node (ref "C19") (pin "1") (pinfunction "1_1") (pintype "passive"))
      (node (ref "HBRIDGE2") (pin "6") (pinfunction "VDD_6") (pintype "power_in"))
      (node (ref "M2SUPPLY") (pin "4") (pinfunction "OUT_4") (pintype "power_in"))
      (node (ref "R5") (pin "2") (pinfunction "P$2_2") (pintype "passive"))
      (node (ref "V+M2") (pin "A") (pinfunction "A_A") (pintype "bidirectional"))
    )
    (net (code "59") (name "unconnected-(CONTROLLERA-P0.2-Pad19)") (class "Default")
      (node (ref "CONTROLLER") (pin "19") (pinfunction "P0.2_19") (pintype "bidirectional"))
    )
    (net (code "60") (name "unconnected-(CONTROLLERB-P1.0-Pad16)") (class "Default")
      (node (ref "CONTROLLER") (pin "16") (pinfunction "P1.0_16") (pintype "bidirectional"))
    )
    (net (code "61") (name "unconnected-(CONTROLLERC-P2.0-Pad35)") (class "Default")
      (node (ref "CONTROLLER") (pin "35") (pinfunction "P2.0_35") (pintype "bidirectional"))
    )
    (net (code "62") (name "unconnected-(CONTROLLERC-P2.1-Pad36)") (class "Default")
      (node (ref "CONTROLLER") (pin "36") (pinfunction "P2.1_36") (pintype "bidirectional"))
    )
    (net (code "63") (name "unconnected-(CONTROLLERC-P2.2-Pad37)") (class "Default")
      (node (ref "CONTROLLER") (pin "37") (pinfunction "P2.2_37") (pintype "input"))
    )
    (net (code "64") (name "unconnected-(CONTROLLERC-P2.3-Pad38)") (class "Default")
      (node (ref "CONTROLLER") (pin "38") (pinfunction "P2.3_38") (pintype "input"))
    )
    (net (code "65") (name "unconnected-(CONTROLLERC-P2.4-Pad1)") (class "Default")
      (node (ref "CONTROLLER") (pin "1") (pinfunction "P2.4_1") (pintype "input"))
    )
    (net (code "66") (name "unconnected-(CONTROLLERC-P2.5-Pad2)") (class "Default")
      (node (ref "CONTROLLER") (pin "2") (pinfunction "P2.5_2") (pintype "input"))
    )
    (net (code "67") (name "unconnected-(CONTROLLERC-P2.6-Pad3)") (class "Default")
      (node (ref "CONTROLLER") (pin "3") (pinfunction "P2.6_3") (pintype "input"))
    )
    (net (code "68") (name "unconnected-(CONTROLLERC-P2.7-Pad4)") (class "Default")
      (node (ref "CONTROLLER") (pin "4") (pinfunction "P2.7_4") (pintype "input"))
    )
    (net (code "69") (name "unconnected-(CONTROLLERC-P2.8-Pad5)") (class "Default")
      (node (ref "CONTROLLER") (pin "5") (pinfunction "P2.8_5") (pintype "input"))
    )
    (net (code "70") (name "unconnected-(CONTROLLERC-P2.9-Pad6)") (class "Default")
      (node (ref "CONTROLLER") (pin "6") (pinfunction "P2.9_6") (pintype "input"))
    )
    (net (code "71") (name "unconnected-(CONTROLLERC-P2.10-Pad7)") (class "Default")
      (node (ref "CONTROLLER") (pin "7") (pinfunction "P2.10_7") (pintype "bidirectional"))
    )
    (net (code "72") (name "unconnected-(CONTROLLERC-P2.11-Pad8)") (class "Default")
      (node (ref "CONTROLLER") (pin "8") (pinfunction "P2.11_8") (pintype "bidirectional"))
    )
    (net (code "73") (name "unconnected-(HBRIDGE1-EF-Pad2)") (class "Default")
      (node (ref "HBRIDGE1") (pin "2") (pinfunction "EF_2") (pintype "output"))
    )
    (net (code "74") (name "unconnected-(HBRIDGE2-EF-Pad2)") (class "Default")
      (node (ref "HBRIDGE2") (pin "2") (pinfunction "EF_2") (pintype "output"))
    )
    (net (code "75") (name "unconnected-(MAIN-2-PadP$3)") (class "Default")
      (node (ref "MAIN") (pin "P$3") (pinfunction "2_P$3") (pintype "bidirectional"))
    )
    (net (code "76") (name "unconnected-(U$2-PadP$1)") (class "Default")
      (node (ref "U$2") (pin "P$1") (pinfunction "P$1_P$1") (pintype "bidirectional"))
    )
    (net (code "77") (name "unconnected-(U$3-PadP$1)") (class "Default")
      (node (ref "U$3") (pin "P$1") (pinfunction "P$1_P$1") (pintype "bidirectional"))
    )
    (net (code "78") (name "unconnected-(U$4-PadP$1)") (class "Default")
      (node (ref "U$4") (pin "P$1") (pinfunction "P$1_P$1") (pintype "bidirectional"))
    )
    (net (code "79") (name "unconnected-(U$5-PadP$1)") (class "Default")
      (node (ref "U$5") (pin "P$1") (pinfunction "P$1_P$1") (pintype "bidirectional"))
    )
  )
)
